# CH4D3M0_Shield.net
KiCad netlist of a schematic drawn in EAGLE
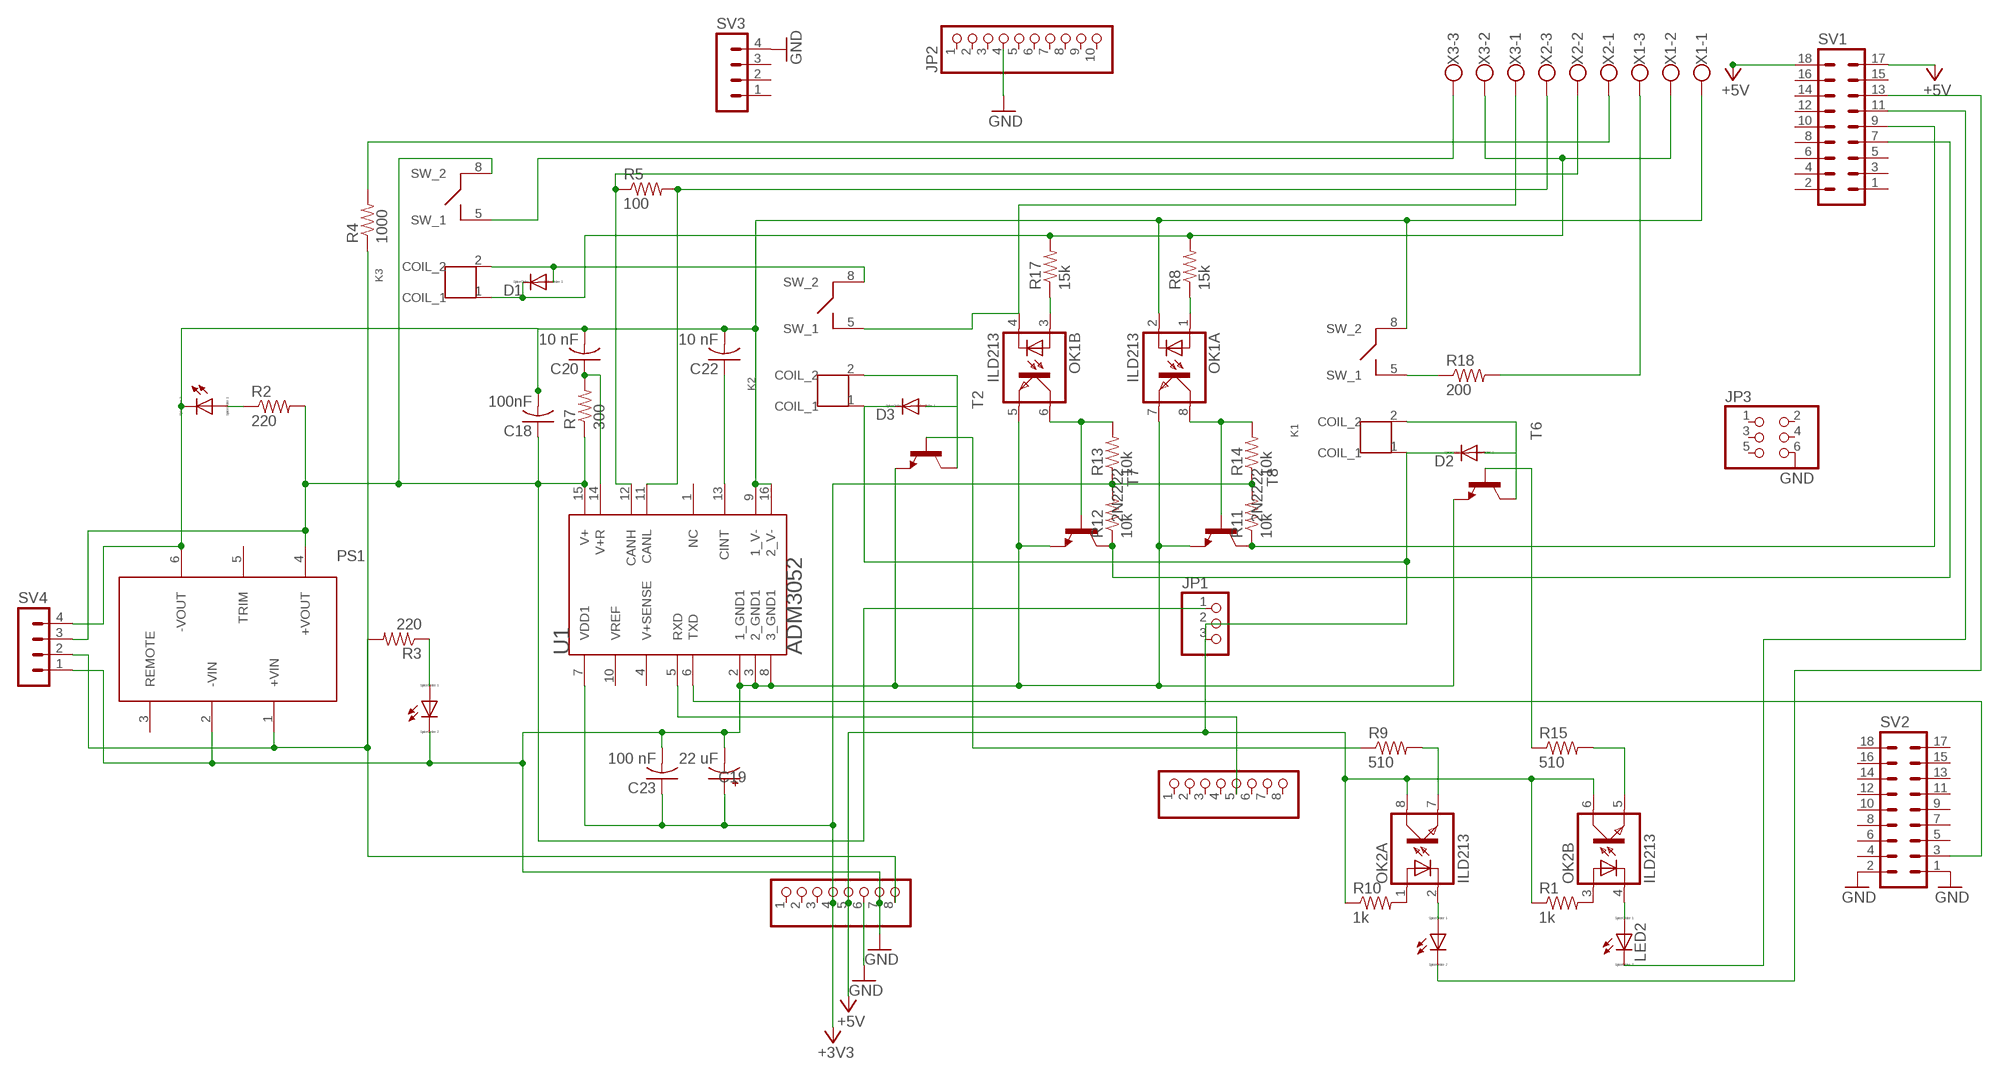
[diagram p0: schematic, sheet 1]

(export (version "E")
  (design (tool "Eeschema 10.0.6"))
  (components
    (comp (ref "ADCH")
      (value "PINHD-1X8")
      (footprint "eagle-import:1X08")
      (libsource (lib "eagle-import") (part "PINHD-1X8"))
    )
    (comp (ref "ADCH2")
      (value "PINHD-1X8")
      (footprint "eagle-import:1X08")
      (libsource (lib "eagle-import") (part "PINHD-1X8"))
    )
    (comp (ref "C18")
      (value "100nF")
      (footprint "eagle-import:C025-024X044")
      (libsource (lib "eagle-import") (part "C-US025-024X044"))
    )
    (comp (ref "C19")
      (value "22 uF")
      (footprint "eagle-import:E2,5RE")
      (libsource (lib "eagle-import") (part "CPOL-USE2.5-4V"))
    )
    (comp (ref "C20")
      (value "10 nF")
      (footprint "eagle-import:C025-024X044")
      (libsource (lib "eagle-import") (part "C-US025-024X044"))
    )
    (comp (ref "C22")
      (value "10 nF")
      (footprint "eagle-import:C025-024X044")
      (libsource (lib "eagle-import") (part "C-US025-024X044"))
    )
    (comp (ref "C23")
      (value "100 nF")
      (footprint "eagle-import:C025-024X044")
      (libsource (lib "eagle-import") (part "C-US025-024X044"))
    )
    (comp (ref "D1")
      (value "DIODE-D-5")
      (footprint "eagle-import:D-5")
      (libsource (lib "eagle-import") (part "DIODE-D-5"))
    )
    (comp (ref "D2")
      (value "DIODE-D-5")
      (footprint "eagle-import:D-5")
      (libsource (lib "eagle-import") (part "DIODE-D-5"))
    )
    (comp (ref "D3")
      (value "DIODE-D-5")
      (footprint "eagle-import:D-5")
      (libsource (lib "eagle-import") (part "DIODE-D-5"))
    )
    (comp (ref "JP1")
      (value "PINHD-1X3")
      (footprint "eagle-import:1X03")
      (libsource (lib "eagle-import") (part "PINHD-1X3"))
    )
    (comp (ref "JP2")
      (value "PINHD-1X10")
      (footprint "eagle-import:1X10")
      (libsource (lib "eagle-import") (part "PINHD-1X10"))
    )
    (comp (ref "JP3")
      (value "PINHD-2X3")
      (footprint "eagle-import:2X03")
      (libsource (lib "eagle-import") (part "PINHD-2X3"))
    )
    (comp (ref "K1")
      (value "G6DN-1ATHROUGH_HOLE")
      (footprint "eagle-import:G6DN-1A")
      (libsource (lib "eagle-import") (part "G6DN-1ATHROUGH_HOLE"))
    )
    (comp (ref "K2")
      (value "G6DN-1ATHROUGH_HOLE")
      (footprint "eagle-import:G6DN-1A")
      (libsource (lib "eagle-import") (part "G6DN-1ATHROUGH_HOLE"))
    )
    (comp (ref "K3")
      (value "G6DN-1ATHROUGH_HOLE")
      (footprint "eagle-import:G6DN-1A")
      (libsource (lib "eagle-import") (part "G6DN-1ATHROUGH_HOLE"))
    )
    (comp (ref "LED1")
      (value "LED_ELD260")
      (footprint "eagle-import:LED_LD260")
      (libsource (lib "eagle-import") (part "LED_ELD260"))
    )
    (comp (ref "LED2")
      (value "LED_ELD260")
      (footprint "eagle-import:LED_LD260")
      (libsource (lib "eagle-import") (part "LED_ELD260"))
    )
    (comp (ref "LED3")
      (value "LED_ELD260")
      (footprint "eagle-import:LED_LD260")
      (libsource (lib "eagle-import") (part "LED_ELD260"))
    )
    (comp (ref "LED4")
      (value "LED_ELD260")
      (footprint "eagle-import:LED_LD260")
      (libsource (lib "eagle-import") (part "LED_ELD260"))
    )
    (comp (ref "OK1")
      (value "ILD213")
      (footprint "eagle-import:SOIC08")
      (fields (field (name "MF") "VISHAY/TELEFUNKEN") (field (name "MPN") "ILD213T"))
      (libsource (lib "eagle-import") (part "ILD213"))
    )
    (comp (ref "OK2")
      (value "ILD213")
      (footprint "eagle-import:SOIC08")
      (fields (field (name "MF") "VISHAY/TELEFUNKEN") (field (name "MPN") "ILD213T"))
      (libsource (lib "eagle-import") (part "ILD213"))
    )
    (comp (ref "PS1")
      (value "JCMXXTHROUGH_HOLE")
      (footprint "eagle-import:JCMXX")
      (libsource (lib "eagle-import") (part "JCMXXTHROUGH_HOLE"))
    )
    (comp (ref "R1")
      (value "1k")
      (footprint "eagle-import:0204_7")
      (libsource (lib "eagle-import") (part "R-US_0204/7"))
    )
    (comp (ref "R2")
      (value "220")
      (footprint "eagle-import:0204_7")
      (libsource (lib "eagle-import") (part "R-US_0204/7"))
    )
    (comp (ref "R3")
      (value "220")
      (footprint "eagle-import:0204_7")
      (libsource (lib "eagle-import") (part "R-US_0204/7"))
    )
    (comp (ref "R4")
      (value "1000")
      (footprint "eagle-import:0204_7")
      (libsource (lib "eagle-import") (part "R-US_0204/7"))
    )
    (comp (ref "R5")
      (value "100")
      (footprint "eagle-import:0204_7")
      (libsource (lib "eagle-import") (part "R-US_0204/7"))
    )
    (comp (ref "R7")
      (value "300")
      (footprint "eagle-import:0204_7")
      (libsource (lib "eagle-import") (part "R-US_0204/7"))
    )
    (comp (ref "R8")
      (value "15k")
      (footprint "eagle-import:0204_7")
      (libsource (lib "eagle-import") (part "R-US_0204/7"))
    )
    (comp (ref "R9")
      (value "510")
      (footprint "eagle-import:0204_7")
      (libsource (lib "eagle-import") (part "R-US_0204/7"))
    )
    (comp (ref "R10")
      (value "1k")
      (footprint "eagle-import:0204_7")
      (libsource (lib "eagle-import") (part "R-US_0204/7"))
    )
    (comp (ref "R11")
      (value "10k")
      (footprint "eagle-import:0204_7")
      (libsource (lib "eagle-import") (part "R-US_0204/7"))
    )
    (comp (ref "R12")
      (value "10k")
      (footprint "eagle-import:0204_7")
      (libsource (lib "eagle-import") (part "R-US_0204/7"))
    )
    (comp (ref "R13")
      (value "10k")
      (footprint "eagle-import:0204_7")
      (libsource (lib "eagle-import") (part "R-US_0204/7"))
    )
    (comp (ref "R14")
      (value "10k")
      (footprint "eagle-import:0204_7")
      (libsource (lib "eagle-import") (part "R-US_0204/7"))
    )
    (comp (ref "R15")
      (value "510")
      (footprint "eagle-import:0204_7")
      (libsource (lib "eagle-import") (part "R-US_0204/7"))
    )
    (comp (ref "R17")
      (value "15k")
      (footprint "eagle-import:0204_7")
      (libsource (lib "eagle-import") (part "R-US_0204/7"))
    )
    (comp (ref "R18")
      (value "200")
      (footprint "eagle-import:0204_7")
      (libsource (lib "eagle-import") (part "R-US_0204/7"))
    )
    (comp (ref "SV1")
      (value "MA09-2")
      (footprint "eagle-import:MA09-2")
      (libsource (lib "eagle-import") (part "MA09-2"))
    )
    (comp (ref "SV2")
      (value "MA09-2")
      (footprint "eagle-import:MA09-2")
      (libsource (lib "eagle-import") (part "MA09-2"))
    )
    (comp (ref "SV3")
      (value "MA04-1")
      (footprint "eagle-import:MA04-1")
      (libsource (lib "eagle-import") (part "MA04-1"))
    )
    (comp (ref "SV4")
      (value "MA04-1")
      (footprint "eagle-import:MA04-1")
      (libsource (lib "eagle-import") (part "MA04-1"))
    )
    (comp (ref "T2")
      (value "BC547-NPN-TO92-CBE")
      (footprint "eagle-import:TO92-CBE")
      (libsource (lib "eagle-import") (part "-NPN-TO92-CBEBC547"))
    )
    (comp (ref "T6")
      (value "BC547-NPN-TO92-CBE")
      (footprint "eagle-import:TO92-CBE")
      (libsource (lib "eagle-import") (part "-NPN-TO92-CBEBC547"))
    )
    (comp (ref "T7")
      (value "2N2222")
      (footprint "eagle-import:TO92-EBC-OVAL")
      (libsource (lib "eagle-import") (part "2N2222"))
    )
    (comp (ref "T8")
      (value "2N2222")
      (footprint "eagle-import:TO92-EBC-OVAL")
      (libsource (lib "eagle-import") (part "2N2222"))
    )
    (comp (ref "U1")
      (value "ANALOG_DEVICES_INC_ADM3052ANALOG_DEVICES_INC_ADM3052_0_0")
      (footprint "eagle-import:ANALOG_DEVICES_INC_ADM3052_0")
      (fields
        (field (name "DIGIKEY_PART_NUMBER") "ADM3052BRWZ-REEL7")
        (field (name "MF") "Analog Devices Inc")
        (field (name "MOUSER_PART_NUMBER") "584-ADM3052BRWZ-R7")
      )
      (libsource (lib "eagle-import") (part "ANALOG_DEVICES_INC_ADM3052ANALOG_DEVICES_INC_ADM3052_0_0"))
    )
    (comp (ref "X1")
      (value "W237-103")
      (footprint "eagle-import:W237-103")
      (fields (field (name "MPN") "237-103"))
      (libsource (lib "eagle-import") (part "W237-103"))
    )
    (comp (ref "X2")
      (value "W237-103")
      (footprint "eagle-import:W237-103")
      (fields (field (name "MPN") "237-103"))
      (libsource (lib "eagle-import") (part "W237-103"))
    )
    (comp (ref "X3")
      (value "W237-103")
      (footprint "eagle-import:W237-103")
      (fields (field (name "MPN") "237-103"))
      (libsource (lib "eagle-import") (part "W237-103"))
    )
  )
  (nets
    (net (code "1") (name "+3V3") (class "Default")
      (node (ref "ADCH2") (pin "4") (pinfunction "4_4") (pintype "passive"))
      (node (ref "C19") (pin "+") (pinfunction "+_+") (pintype "passive"))
      (node (ref "C23") (pin "1") (pinfunction "1_1") (pintype "passive"))
      (node (ref "R11") (pin "2") (pinfunction "2_2") (pintype "passive"))
      (node (ref "R12") (pin "2") (pinfunction "2_2") (pintype "passive"))
      (node (ref "R13") (pin "1") (pinfunction "1_1") (pintype "passive"))
      (node (ref "R14") (pin "1") (pinfunction "1_1") (pintype "passive"))
      (node (ref "U1") (pin "7") (pinfunction "VDD1_7") (pintype "bidirectional"))
    )
    (net (code "2") (name "+5V") (class "Default")
      (node (ref "ADCH2") (pin "5") (pinfunction "5_5") (pintype "passive"))
      (node (ref "D2") (pin "C") (pinfunction "C_C") (pintype "passive"))
      (node (ref "D3") (pin "C") (pinfunction "C_C") (pintype "passive"))
      (node (ref "JP1") (pin "2") (pinfunction "2_2") (pintype "passive"))
      (node (ref "JP1") (pin "3") (pinfunction "3_3") (pintype "passive"))
      (node (ref "K1") (pin "1") (pinfunction "COIL_1_1") (pintype "bidirectional"))
      (node (ref "K2") (pin "1") (pinfunction "COIL_1_1") (pintype "bidirectional"))
      (node (ref "OK2") (pin "6") (pinfunction "COL_6") (pintype "passive"))
      (node (ref "OK2") (pin "8") (pinfunction "COL_8") (pintype "passive"))
      (node (ref "R1") (pin "1") (pinfunction "1_1") (pintype "passive"))
      (node (ref "R10") (pin "1") (pinfunction "1_1") (pintype "passive"))
      (node (ref "SV1") (pin "17") (pinfunction "17_17") (pintype "passive"))
      (node (ref "SV1") (pin "18") (pinfunction "18_18") (pintype "passive"))
    )
    (net (code "3") (name "GND") (class "Default")
      (node (ref "ADCH2") (pin "6") (pinfunction "6_6") (pintype "passive"))
      (node (ref "ADCH2") (pin "7") (pinfunction "7_7") (pintype "passive"))
      (node (ref "C19") (pin "-") (pinfunction "-_-") (pintype "passive"))
      (node (ref "C23") (pin "2") (pinfunction "2_2") (pintype "passive"))
      (node (ref "JP2") (pin "4") (pinfunction "4_4") (pintype "passive"))
      (node (ref "JP3") (pin "6") (pinfunction "6_6") (pintype "passive"))
      (node (ref "LED4") (pin "K") (pinfunction "C_K") (pintype "passive"))
      (node (ref "OK1") (pin "5") (pinfunction "EMIT_5") (pintype "passive"))
      (node (ref "OK1") (pin "7") (pinfunction "EMIT_7") (pintype "passive"))
      (node (ref "PS1") (pin "2") (pinfunction "-VIN_2") (pintype "power_in"))
      (node (ref "SV2") (pin "1") (pinfunction "1_1") (pintype "passive"))
      (node (ref "SV2") (pin "2") (pinfunction "2_2") (pintype "passive"))
      (node (ref "SV3") (pin "4") (pinfunction "4_4") (pintype "passive"))
      (node (ref "SV4") (pin "1") (pinfunction "1_1") (pintype "passive"))
      (node (ref "T2") (pin "E") (pinfunction "E_E") (pintype "passive"))
      (node (ref "T6") (pin "E") (pinfunction "E_E") (pintype "passive"))
      (node (ref "T7") (pin "E") (pinfunction "E_E") (pintype "passive"))
      (node (ref "T8") (pin "E") (pinfunction "E_E") (pintype "passive"))
      (node (ref "U1") (pin "2") (pinfunction "1_GND1_2") (pintype "bidirectional"))
      (node (ref "U1") (pin "3") (pinfunction "2_GND1_3") (pintype "bidirectional"))
      (node (ref "U1") (pin "8") (pinfunction "3_GND1_8") (pintype "bidirectional"))
    )
    (net (code "4") (name "Net-(K1-COIL_2)") (class "Default")
      (node (ref "D2") (pin "A") (pinfunction "A_A") (pintype "passive"))
      (node (ref "K1") (pin "2") (pinfunction "COIL_2_2") (pintype "bidirectional"))
      (node (ref "T6") (pin "C") (pinfunction "C_C") (pintype "passive"))
    )
    (net (code "5") (name "Net-(K1-SW_1)") (class "Default")
      (node (ref "K1") (pin "5") (pinfunction "SW_1_5") (pintype "bidirectional"))
      (node (ref "R18") (pin "1") (pinfunction "1_1") (pintype "passive"))
    )
    (net (code "6") (name "Net-(K1-SW_2)") (class "Default")
      (node (ref "C18") (pin "2") (pinfunction "2_2") (pintype "passive"))
      (node (ref "C20") (pin "2") (pinfunction "2_2") (pintype "passive"))
      (node (ref "C22") (pin "2") (pinfunction "2_2") (pintype "passive"))
      (node (ref "K1") (pin "8") (pinfunction "SW_2_8") (pintype "bidirectional"))
      (node (ref "LED3") (pin "K") (pinfunction "C_K") (pintype "passive"))
      (node (ref "OK1") (pin "2") (pinfunction "C_2") (pintype "passive"))
      (node (ref "PS1") (pin "6") (pinfunction "-VOUT_6") (pintype "output"))
      (node (ref "SV4") (pin "4") (pinfunction "4_4") (pintype "passive"))
      (node (ref "U1") (pin "16") (pinfunction "2_V-_16") (pintype "bidirectional"))
      (node (ref "U1") (pin "9") (pinfunction "1_V-_9") (pintype "bidirectional"))
      (node (ref "X1") (pin "1") (pinfunction "KL_1") (pintype "passive"))
    )
    (net (code "7") (name "Net-(K2-COIL_2)") (class "Default")
      (node (ref "D3") (pin "A") (pinfunction "A_A") (pintype "passive"))
      (node (ref "K2") (pin "2") (pinfunction "COIL_2_2") (pintype "bidirectional"))
      (node (ref "T2") (pin "C") (pinfunction "C_C") (pintype "passive"))
    )
    (net (code "8") (name "Net-(K2-SW_1)") (class "Default")
      (node (ref "K2") (pin "5") (pinfunction "SW_1_5") (pintype "bidirectional"))
      (node (ref "OK1") (pin "4") (pinfunction "C_4") (pintype "passive"))
      (node (ref "X3") (pin "1") (pinfunction "KL_1") (pintype "passive"))
    )
    (net (code "9") (name "Net-(K2-SW_2)") (class "Default")
      (node (ref "D1") (pin "A") (pinfunction "A_A") (pintype "passive"))
      (node (ref "K2") (pin "8") (pinfunction "SW_2_8") (pintype "bidirectional"))
      (node (ref "K3") (pin "2") (pinfunction "COIL_2_2") (pintype "bidirectional"))
    )
    (net (code "10") (name "Net-(K3-COIL_1)") (class "Default")
      (node (ref "D1") (pin "C") (pinfunction "C_C") (pintype "passive"))
      (node (ref "K3") (pin "1") (pinfunction "COIL_1_1") (pintype "bidirectional"))
      (node (ref "R17") (pin "2") (pinfunction "2_2") (pintype "passive"))
      (node (ref "R8") (pin "2") (pinfunction "2_2") (pintype "passive"))
      (node (ref "X1") (pin "2") (pinfunction "KL_2") (pintype "passive"))
      (node (ref "X3") (pin "2") (pinfunction "KL_2") (pintype "passive"))
    )
    (net (code "11") (name "Net-(K3-SW_1)") (class "Default")
      (node (ref "K3") (pin "5") (pinfunction "SW_1_5") (pintype "bidirectional"))
      (node (ref "X3") (pin "3") (pinfunction "KL_3") (pintype "passive"))
    )
    (net (code "12") (name "Net-(K3-SW_2)") (class "Default")
      (node (ref "C18") (pin "1") (pinfunction "1_1") (pintype "passive"))
      (node (ref "JP1") (pin "1") (pinfunction "1_1") (pintype "passive"))
      (node (ref "K3") (pin "8") (pinfunction "SW_2_8") (pintype "bidirectional"))
      (node (ref "PS1") (pin "4") (pinfunction "+VOUT_4") (pintype "output"))
      (node (ref "R2") (pin "2") (pinfunction "2_2") (pintype "passive"))
      (node (ref "R7") (pin "1") (pinfunction "1_1") (pintype "passive"))
      (node (ref "SV4") (pin "3") (pinfunction "3_3") (pintype "passive"))
      (node (ref "U1") (pin "15") (pinfunction "V+_15") (pintype "bidirectional"))
    )
    (net (code "13") (name "Net-(LED1-C)") (class "Default")
      (node (ref "LED1") (pin "K") (pinfunction "C_K") (pintype "passive"))
      (node (ref "SV1") (pin "13") (pinfunction "13_13") (pintype "passive"))
    )
    (net (code "14") (name "Net-(LED2-C)") (class "Default")
      (node (ref "LED2") (pin "K") (pinfunction "C_K") (pintype "passive"))
      (node (ref "SV1") (pin "11") (pinfunction "11_11") (pintype "passive"))
    )
    (net (code "15") (name "Net-(LED3-PadA)") (class "Default")
      (node (ref "LED3") (pin "A") (pinfunction "A_A") (pintype "passive"))
      (node (ref "R2") (pin "1") (pinfunction "1_1") (pintype "passive"))
    )
    (net (code "16") (name "Net-(LED4-PadA)") (class "Default")
      (node (ref "LED4") (pin "A") (pinfunction "A_A") (pintype "passive"))
      (node (ref "R3") (pin "1") (pinfunction "1_1") (pintype "passive"))
    )
    (net (code "17") (name "Net-(OK1A-A)") (class "Default")
      (node (ref "OK1") (pin "1") (pinfunction "A_1") (pintype "passive"))
      (node (ref "R8") (pin "1") (pinfunction "1_1") (pintype "passive"))
    )
    (net (code "18") (name "Net-(OK1A-COL)") (class "Default")
      (node (ref "OK1") (pin "8") (pinfunction "COL_8") (pintype "passive"))
      (node (ref "R14") (pin "2") (pinfunction "2_2") (pintype "passive"))
      (node (ref "T8") (pin "B") (pinfunction "B_B") (pintype "passive"))
    )
    (net (code "19") (name "Net-(OK1B-A)") (class "Default")
      (node (ref "OK1") (pin "3") (pinfunction "A_3") (pintype "passive"))
      (node (ref "R17") (pin "1") (pinfunction "1_1") (pintype "passive"))
    )
    (net (code "20") (name "Net-(OK1B-COL)") (class "Default")
      (node (ref "OK1") (pin "6") (pinfunction "COL_6") (pintype "passive"))
      (node (ref "R13") (pin "2") (pinfunction "2_2") (pintype "passive"))
      (node (ref "T7") (pin "B") (pinfunction "B_B") (pintype "passive"))
    )
    (net (code "21") (name "Net-(OK2A-A)") (class "Default")
      (node (ref "OK2") (pin "1") (pinfunction "A_1") (pintype "passive"))
      (node (ref "R10") (pin "2") (pinfunction "2_2") (pintype "passive"))
    )
    (net (code "22") (name "Net-(OK2A-C)") (class "Default")
      (node (ref "LED1") (pin "A") (pinfunction "A_A") (pintype "passive"))
      (node (ref "OK2") (pin "2") (pinfunction "C_2") (pintype "passive"))
    )
    (net (code "23") (name "Net-(OK2A-EMIT)") (class "Default")
      (node (ref "OK2") (pin "7") (pinfunction "EMIT_7") (pintype "passive"))
      (node (ref "R9") (pin "2") (pinfunction "2_2") (pintype "passive"))
    )
    (net (code "24") (name "Net-(OK2B-A)") (class "Default")
      (node (ref "OK2") (pin "3") (pinfunction "A_3") (pintype "passive"))
      (node (ref "R1") (pin "2") (pinfunction "2_2") (pintype "passive"))
    )
    (net (code "25") (name "Net-(OK2B-C)") (class "Default")
      (node (ref "LED2") (pin "A") (pinfunction "A_A") (pintype "passive"))
      (node (ref "OK2") (pin "4") (pinfunction "C_4") (pintype "passive"))
    )
    (net (code "26") (name "Net-(OK2B-EMIT)") (class "Default")
      (node (ref "OK2") (pin "5") (pinfunction "EMIT_5") (pintype "passive"))
      (node (ref "R15") (pin "2") (pinfunction "2_2") (pintype "passive"))
    )
    (net (code "27") (name "Net-(PS1-+VIN)") (class "Default")
      (node (ref "ADCH2") (pin "8") (pinfunction "8_8") (pintype "passive"))
      (node (ref "PS1") (pin "1") (pinfunction "+VIN_1") (pintype "power_in"))
      (node (ref "R3") (pin "2") (pinfunction "2_2") (pintype "passive"))
      (node (ref "R4") (pin "1") (pinfunction "1_1") (pintype "passive"))
      (node (ref "SV4") (pin "2") (pinfunction "2_2") (pintype "passive"))
    )
    (net (code "28") (name "Net-(R9-Pad1)") (class "Default")
      (node (ref "R9") (pin "1") (pinfunction "1_1") (pintype "passive"))
      (node (ref "T2") (pin "B") (pinfunction "B_B") (pintype "passive"))
    )
    (net (code "29") (name "Net-(R11-Pad1)") (class "Default")
      (node (ref "R11") (pin "1") (pinfunction "1_1") (pintype "passive"))
      (node (ref "SV1") (pin "9") (pinfunction "9_9") (pintype "passive"))
      (node (ref "T8") (pin "C") (pinfunction "C_C") (pintype "passive"))
    )
    (net (code "30") (name "Net-(R12-Pad1)") (class "Default")
      (node (ref "R12") (pin "1") (pinfunction "1_1") (pintype "passive"))
      (node (ref "SV1") (pin "7") (pinfunction "7_7") (pintype "passive"))
      (node (ref "T7") (pin "C") (pinfunction "C_C") (pintype "passive"))
    )
    (net (code "31") (name "Net-(R15-Pad1)") (class "Default")
      (node (ref "R15") (pin "1") (pinfunction "1_1") (pintype "passive"))
      (node (ref "T6") (pin "B") (pinfunction "B_B") (pintype "passive"))
    )
    (net (code "32") (name "Net-(U1-CANH)") (class "Default")
      (node (ref "R5") (pin "1") (pinfunction "1_1") (pintype "passive"))
      (node (ref "U1") (pin "12") (pinfunction "CANH_12") (pintype "bidirectional"))
      (node (ref "X2") (pin "2") (pinfunction "KL_2") (pintype "passive"))
    )
    (net (code "33") (name "Net-(U1-CANL)") (class "Default")
      (node (ref "R5") (pin "2") (pinfunction "2_2") (pintype "passive"))
      (node (ref "U1") (pin "11") (pinfunction "CANL_11") (pintype "bidirectional"))
      (node (ref "X2") (pin "3") (pinfunction "KL_3") (pintype "passive"))
    )
    (net (code "34") (name "Net-(U1-CINT)") (class "Default")
      (node (ref "C22") (pin "1") (pinfunction "1_1") (pintype "passive"))
      (node (ref "U1") (pin "13") (pinfunction "CINT_13") (pintype "bidirectional"))
    )
    (net (code "35") (name "Net-(U1-RXD)") (class "Default")
      (node (ref "ADCH") (pin "5") (pinfunction "5_5") (pintype "passive"))
      (node (ref "U1") (pin "5") (pinfunction "RXD_5") (pintype "bidirectional"))
    )
    (net (code "36") (name "Net-(U1-TXD)") (class "Default")
      (node (ref "SV2") (pin "3") (pinfunction "3_3") (pintype "passive"))
      (node (ref "U1") (pin "6") (pinfunction "TXD_6") (pintype "bidirectional"))
    )
    (net (code "37") (name "Net-(U1-V+R)") (class "Default")
      (node (ref "C20") (pin "1") (pinfunction "1_1") (pintype "passive"))
      (node (ref "R7") (pin "2") (pinfunction "2_2") (pintype "passive"))
      (node (ref "U1") (pin "14") (pinfunction "V+R_14") (pintype "bidirectional"))
    )
    (net (code "38") (name "Net-(X1C-KL)") (class "Default")
      (node (ref "R18") (pin "2") (pinfunction "2_2") (pintype "passive"))
      (node (ref "X1") (pin "3") (pinfunction "KL_3") (pintype "passive"))
    )
    (net (code "39") (name "Net-(X2A-KL)") (class "Default")
      (node (ref "R4") (pin "2") (pinfunction "2_2") (pintype "passive"))
      (node (ref "X2") (pin "1") (pinfunction "KL_1") (pintype "passive"))
    )
    (net (code "40") (name "unconnected-(ADCH-Pad1)") (class "Default")
      (node (ref "ADCH") (pin "1") (pinfunction "1_1") (pintype "passive"))
    )
    (net (code "41") (name "unconnected-(ADCH-Pad2)") (class "Default")
      (node (ref "ADCH") (pin "2") (pinfunction "2_2") (pintype "passive"))
    )
    (net (code "42") (name "unconnected-(ADCH-Pad3)") (class "Default")
      (node (ref "ADCH") (pin "3") (pinfunction "3_3") (pintype "passive"))
    )
    (net (code "43") (name "unconnected-(ADCH-Pad4)") (class "Default")
      (node (ref "ADCH") (pin "4") (pinfunction "4_4") (pintype "passive"))
    )
    (net (code "44") (name "unconnected-(ADCH-Pad6)") (class "Default")
      (node (ref "ADCH") (pin "6") (pinfunction "6_6") (pintype "passive"))
    )
    (net (code "45") (name "unconnected-(ADCH-Pad7)") (class "Default")
      (node (ref "ADCH") (pin "7") (pinfunction "7_7") (pintype "passive"))
    )
    (net (code "46") (name "unconnected-(ADCH-Pad8)") (class "Default")
      (node (ref "ADCH") (pin "8") (pinfunction "8_8") (pintype "passive"))
    )
    (net (code "47") (name "unconnected-(ADCH2-Pad1)") (class "Default")
      (node (ref "ADCH2") (pin "1") (pinfunction "1_1") (pintype "passive"))
    )
    (net (code "48") (name "unconnected-(ADCH2-Pad2)") (class "Default")
      (node (ref "ADCH2") (pin "2") (pinfunction "2_2") (pintype "passive"))
    )
    (net (code "49") (name "unconnected-(ADCH2-Pad3)") (class "Default")
      (node (ref "ADCH2") (pin "3") (pinfunction "3_3") (pintype "passive"))
    )
    (net (code "50") (name "unconnected-(JP2-Pad1)") (class "Default")
      (node (ref "JP2") (pin "1") (pinfunction "1_1") (pintype "passive"))
    )
    (net (code "51") (name "unconnected-(JP2-Pad2)") (class "Default")
      (node (ref "JP2") (pin "2") (pinfunction "2_2") (pintype "passive"))
    )
    (net (code "52") (name "unconnected-(JP2-Pad3)") (class "Default")
      (node (ref "JP2") (pin "3") (pinfunction "3_3") (pintype "passive"))
    )
    (net (code "53") (name "unconnected-(JP2-Pad5)") (class "Default")
      (node (ref "JP2") (pin "5") (pinfunction "5_5") (pintype "passive"))
    )
    (net (code "54") (name "unconnected-(JP2-Pad6)") (class "Default")
      (node (ref "JP2") (pin "6") (pinfunction "6_6") (pintype "passive"))
    )
    (net (code "55") (name "unconnected-(JP2-Pad7)") (class "Default")
      (node (ref "JP2") (pin "7") (pinfunction "7_7") (pintype "passive"))
    )
    (net (code "56") (name "unconnected-(JP2-Pad8)") (class "Default")
      (node (ref "JP2") (pin "8") (pinfunction "8_8") (pintype "passive"))
    )
    (net (code "57") (name "unconnected-(JP2-Pad9)") (class "Default")
      (node (ref "JP2") (pin "9") (pinfunction "9_9") (pintype "passive"))
    )
    (net (code "58") (name "unconnected-(JP2-Pad10)") (class "Default")
      (node (ref "JP2") (pin "10") (pinfunction "10_10") (pintype "passive"))
    )
    (net (code "59") (name "unconnected-(JP3-Pad1)") (class "Default")
      (node (ref "JP3") (pin "1") (pinfunction "1_1") (pintype "passive"))
    )
    (net (code "60") (name "unconnected-(JP3-Pad2)") (class "Default")
      (node (ref "JP3") (pin "2") (pinfunction "2_2") (pintype "passive"))
    )
    (net (code "61") (name "unconnected-(JP3-Pad3)") (class "Default")
      (node (ref "JP3") (pin "3") (pinfunction "3_3") (pintype "passive"))
    )
    (net (code "62") (name "unconnected-(JP3-Pad4)") (class "Default")
      (node (ref "JP3") (pin "4") (pinfunction "4_4") (pintype "passive"))
    )
    (net (code "63") (name "unconnected-(JP3-Pad5)") (class "Default")
      (node (ref "JP3") (pin "5") (pinfunction "5_5") (pintype "passive"))
    )
    (net (code "64") (name "unconnected-(PS1-REMOTE-Pad3)") (class "Default")
      (node (ref "PS1") (pin "3") (pinfunction "REMOTE_3") (pintype "input"))
    )
    (net (code "65") (name "unconnected-(PS1-TRIM-Pad5)") (class "Default")
      (node (ref "PS1") (pin "5") (pinfunction "TRIM_5") (pintype "input"))
    )
    (net (code "66") (name "unconnected-(SV1-Pad1)") (class "Default")
      (node (ref "SV1") (pin "1") (pinfunction "1_1") (pintype "passive"))
    )
    (net (code "67") (name "unconnected-(SV1-Pad2)") (class "Default")
      (node (ref "SV1") (pin "2") (pinfunction "2_2") (pintype "passive"))
    )
    (net (code "68") (name "unconnected-(SV1-Pad3)") (class "Default")
      (node (ref "SV1") (pin "3") (pinfunction "3_3") (pintype "passive"))
    )
    (net (code "69") (name "unconnected-(SV1-Pad4)") (class "Default")
      (node (ref "SV1") (pin "4") (pinfunction "4_4") (pintype "passive"))
    )
    (net (code "70") (name "unconnected-(SV1-Pad5)") (class "Default")
      (node (ref "SV1") (pin "5") (pinfunction "5_5") (pintype "passive"))
    )
    (net (code "71") (name "unconnected-(SV1-Pad6)") (class "Default")
      (node (ref "SV1") (pin "6") (pinfunction "6_6") (pintype "passive"))
    )
    (net (code "72") (name "unconnected-(SV1-Pad8)") (class "Default")
      (node (ref "SV1") (pin "8") (pinfunction "8_8") (pintype "passive"))
    )
    (net (code "73") (name "unconnected-(SV1-Pad10)") (class "Default")
      (node (ref "SV1") (pin "10") (pinfunction "10_10") (pintype "passive"))
    )
    (net (code "74") (name "unconnected-(SV1-Pad12)") (class "Default")
      (node (ref "SV1") (pin "12") (pinfunction "12_12") (pintype "passive"))
    )
    (net (code "75") (name "unconnected-(SV1-Pad14)") (class "Default")
      (node (ref "SV1") (pin "14") (pinfunction "14_14") (pintype "passive"))
    )
    (net (code "76") (name "unconnected-(SV1-Pad15)") (class "Default")
      (node (ref "SV1") (pin "15") (pinfunction "15_15") (pintype "passive"))
    )
    (net (code "77") (name "unconnected-(SV1-Pad16)") (class "Default")
      (node (ref "SV1") (pin "16") (pinfunction "16_16") (pintype "passive"))
    )
    (net (code "78") (name "unconnected-(SV2-Pad4)") (class "Default")
      (node (ref "SV2") (pin "4") (pinfunction "4_4") (pintype "passive"))
    )
    (net (code "79") (name "unconnected-(SV2-Pad5)") (class "Default")
      (node (ref "SV2") (pin "5") (pinfunction "5_5") (pintype "passive"))
    )
    (net (code "80") (name "unconnected-(SV2-Pad6)") (class "Default")
      (node (ref "SV2") (pin "6") (pinfunction "6_6") (pintype "passive"))
    )
    (net (code "81") (name "unconnected-(SV2-Pad7)") (class "Default")
      (node (ref "SV2") (pin "7") (pinfunction "7_7") (pintype "passive"))
    )
    (net (code "82") (name "unconnected-(SV2-Pad8)") (class "Default")
      (node (ref "SV2") (pin "8") (pinfunction "8_8") (pintype "passive"))
    )
    (net (code "83") (name "unconnected-(SV2-Pad9)") (class "Default")
      (node (ref "SV2") (pin "9") (pinfunction "9_9") (pintype "passive"))
    )
    (net (code "84") (name "unconnected-(SV2-Pad10)") (class "Default")
      (node (ref "SV2") (pin "10") (pinfunction "10_10") (pintype "passive"))
    )
    (net (code "85") (name "unconnected-(SV2-Pad11)") (class "Default")
      (node (ref "SV2") (pin "11") (pinfunction "11_11") (pintype "passive"))
    )
    (net (code "86") (name "unconnected-(SV2-Pad12)") (class "Default")
      (node (ref "SV2") (pin "12") (pinfunction "12_12") (pintype "passive"))
    )
    (net (code "87") (name "unconnected-(SV2-Pad13)") (class "Default")
      (node (ref "SV2") (pin "13") (pinfunction "13_13") (pintype "passive"))
    )
    (net (code "88") (name "unconnected-(SV2-Pad14)") (class "Default")
      (node (ref "SV2") (pin "14") (pinfunction "14_14") (pintype "passive"))
    )
    (net (code "89") (name "unconnected-(SV2-Pad15)") (class "Default")
      (node (ref "SV2") (pin "15") (pinfunction "15_15") (pintype "passive"))
    )
    (net (code "90") (name "unconnected-(SV2-Pad16)") (class "Default")
      (node (ref "SV2") (pin "16") (pinfunction "16_16") (pintype "passive"))
    )
    (net (code "91") (name "unconnected-(SV2-Pad17)") (class "Default")
      (node (ref "SV2") (pin "17") (pinfunction "17_17") (pintype "passive"))
    )
    (net (code "92") (name "unconnected-(SV2-Pad18)") (class "Default")
      (node (ref "SV2") (pin "18") (pinfunction "18_18") (pintype "passive"))
    )
    (net (code "93") (name "unconnected-(SV3-Pad1)") (class "Default")
      (node (ref "SV3") (pin "1") (pinfunction "1_1") (pintype "passive"))
    )
    (net (code "94") (name "unconnected-(SV3-Pad2)") (class "Default")
      (node (ref "SV3") (pin "2") (pinfunction "2_2") (pintype "passive"))
    )
    (net (code "95") (name "unconnected-(SV3-Pad3)") (class "Default")
      (node (ref "SV3") (pin "3") (pinfunction "3_3") (pintype "passive"))
    )
    (net (code "96") (name "unconnected-(U1-NC-Pad1)") (class "Default")
      (node (ref "U1") (pin "1") (pinfunction "NC_1") (pintype "bidirectional"))
    )
    (net (code "97") (name "unconnected-(U1-V+SENSE-Pad4)") (class "Default")
      (node (ref "U1") (pin "4") (pinfunction "V+SENSE_4") (pintype "bidirectional"))
    )
    (net (code "98") (name "unconnected-(U1-VREF-Pad10)") (class "Default")
      (node (ref "U1") (pin "10") (pinfunction "VREF_10") (pintype "bidirectional"))
    )
  )
)
